# Wind_enc.net
KiCad netlist of a schematic drawn in EAGLE
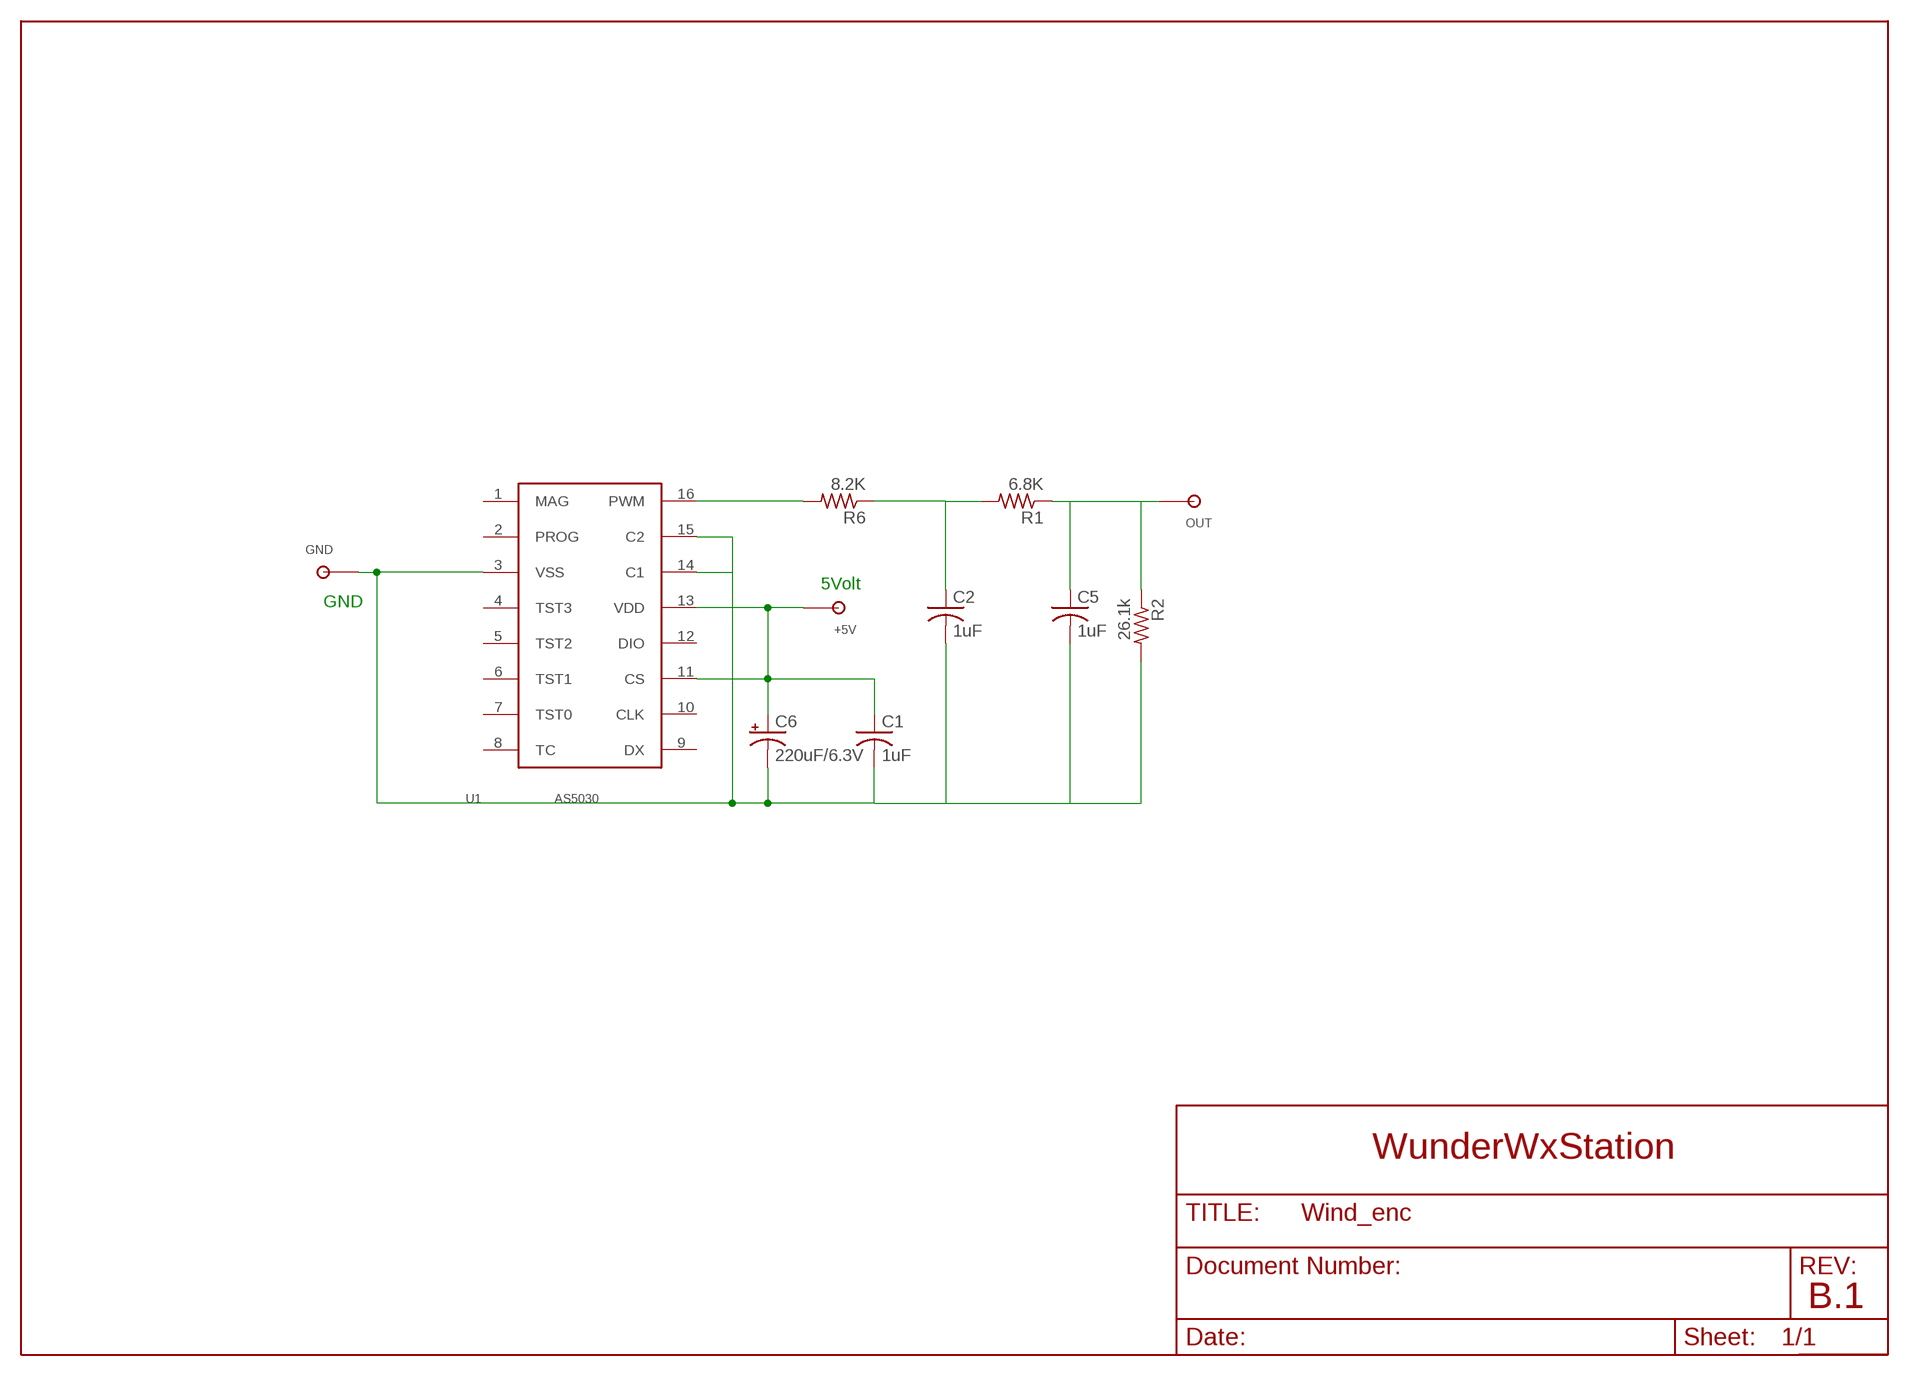
[diagram p0: schematic, sheet 1]

(export (version "E")
  (design (tool "Eeschema 10.0.6"))
  (components
    (comp (ref "+5V")
      (value "TPSOL")
      (footprint "eagle-import:TP_SOL")
      (libsource (lib "eagle-import") (part "TPSOL"))
    )
    (comp (ref "C1")
      (value "1uF")
      (footprint "eagle-import:C0805K")
      (libsource (lib "eagle-import") (part "C-USC0805K"))
    )
    (comp (ref "C2")
      (value "1uF")
      (footprint "eagle-import:C0805K")
      (libsource (lib "eagle-import") (part "C-USC0805K"))
    )
    (comp (ref "C5")
      (value "1uF")
      (footprint "eagle-import:C0805K")
      (libsource (lib "eagle-import") (part "C-USC0805K"))
    )
    (comp (ref "C6")
      (value "220uF/6.3V")
      (footprint "eagle-import:SMC_D")
      (libsource (lib "eagle-import") (part "CPOL-USSMCD"))
    )
    (comp (ref "GND")
      (value "TPSOL")
      (footprint "eagle-import:TP_SOL")
      (libsource (lib "eagle-import") (part "TPSOL"))
    )
    (comp (ref "OUT")
      (value "TPSOL")
      (footprint "eagle-import:TP_SOL")
      (libsource (lib "eagle-import") (part "TPSOL"))
    )
    (comp (ref "R1")
      (value "6.8K")
      (footprint "eagle-import:R0603")
      (libsource (lib "eagle-import") (part "R-US_R0603"))
    )
    (comp (ref "R2")
      (value "26.1k")
      (footprint "eagle-import:R0603")
      (libsource (lib "eagle-import") (part "R-US_R0603"))
    )
    (comp (ref "R6")
      (value "8.2K")
      (footprint "eagle-import:R0603")
      (libsource (lib "eagle-import") (part "R-US_R0603"))
    )
    (comp (ref "U1")
      (value "AS5030")
      (footprint "eagle-import:TSSOP16")
      (libsource (lib "eagle-import") (part "AS5030"))
    )
  )
  (nets
    (net (code "1") (name "Net-(C2-Pad1)") (class "Default")
      (node (ref "C2") (pin "1") (pinfunction "1_1") (pintype "passive"))
      (node (ref "R1") (pin "2") (pinfunction "2_2") (pintype "passive"))
      (node (ref "R6") (pin "1") (pinfunction "1_1") (pintype "passive"))
    )
    (net (code "2") (name "Net-(C5-Pad1)") (class "Default")
      (node (ref "C5") (pin "1") (pinfunction "1_1") (pintype "passive"))
      (node (ref "OUT") (pin "P$1") (pinfunction "P$1_P$1") (pintype "bidirectional"))
      (node (ref "R1") (pin "1") (pinfunction "1_1") (pintype "passive"))
      (node (ref "R2") (pin "1") (pinfunction "1_1") (pintype "passive"))
    )
    (net (code "3") (name "Net-(U1-C1)") (class "Default")
      (node (ref "C1") (pin "2") (pinfunction "2_2") (pintype "passive"))
      (node (ref "C2") (pin "2") (pinfunction "2_2") (pintype "passive"))
      (node (ref "C5") (pin "2") (pinfunction "2_2") (pintype "passive"))
      (node (ref "C6") (pin "-") (pinfunction "-_-") (pintype "passive"))
      (node (ref "GND") (pin "P$1") (pinfunction "P$1_P$1") (pintype "bidirectional"))
      (node (ref "R2") (pin "2") (pinfunction "2_2") (pintype "passive"))
      (node (ref "U1") (pin "14") (pinfunction "C1_14") (pintype "bidirectional"))
      (node (ref "U1") (pin "15") (pinfunction "C2_15") (pintype "bidirectional"))
      (node (ref "U1") (pin "3") (pinfunction "VSS_3") (pintype "bidirectional"))
    )
    (net (code "4") (name "Net-(U1-CS)") (class "Default")
      (node (ref "+5V") (pin "P$1") (pinfunction "P$1_P$1") (pintype "bidirectional"))
      (node (ref "C1") (pin "1") (pinfunction "1_1") (pintype "passive"))
      (node (ref "C6") (pin "+") (pinfunction "+_+") (pintype "passive"))
      (node (ref "U1") (pin "11") (pinfunction "CS_11") (pintype "bidirectional"))
      (node (ref "U1") (pin "13") (pinfunction "VDD_13") (pintype "bidirectional"))
    )
    (net (code "5") (name "Net-(U1-PWM)") (class "Default")
      (node (ref "R6") (pin "2") (pinfunction "2_2") (pintype "passive"))
      (node (ref "U1") (pin "16") (pinfunction "PWM_16") (pintype "bidirectional"))
    )
    (net (code "6") (name "unconnected-(U1-CLK-Pad10)") (class "Default")
      (node (ref "U1") (pin "10") (pinfunction "CLK_10") (pintype "bidirectional"))
    )
    (net (code "7") (name "unconnected-(U1-DIO-Pad12)") (class "Default")
      (node (ref "U1") (pin "12") (pinfunction "DIO_12") (pintype "bidirectional"))
    )
    (net (code "8") (name "unconnected-(U1-DX-Pad9)") (class "Default")
      (node (ref "U1") (pin "9") (pinfunction "DX_9") (pintype "bidirectional"))
    )
    (net (code "9") (name "unconnected-(U1-MAG-Pad1)") (class "Default")
      (node (ref "U1") (pin "1") (pinfunction "MAG_1") (pintype "bidirectional"))
    )
    (net (code "10") (name "unconnected-(U1-PROG-Pad2)") (class "Default")
      (node (ref "U1") (pin "2") (pinfunction "PROG_2") (pintype "bidirectional"))
    )
    (net (code "11") (name "unconnected-(U1-TC-Pad8)") (class "Default")
      (node (ref "U1") (pin "8") (pinfunction "TC_8") (pintype "bidirectional"))
    )
    (net (code "12") (name "unconnected-(U1-TST0-Pad7)") (class "Default")
      (node (ref "U1") (pin "7") (pinfunction "TST0_7") (pintype "bidirectional"))
    )
    (net (code "13") (name "unconnected-(U1-TST1-Pad6)") (class "Default")
      (node (ref "U1") (pin "6") (pinfunction "TST1_6") (pintype "bidirectional"))
    )
    (net (code "14") (name "unconnected-(U1-TST2-Pad5)") (class "Default")
      (node (ref "U1") (pin "5") (pinfunction "TST2_5") (pintype "bidirectional"))
    )
    (net (code "15") (name "unconnected-(U1-TST3-Pad4)") (class "Default")
      (node (ref "U1") (pin "4") (pinfunction "TST3_4") (pintype "bidirectional"))
    )
  )
)
